# GSM.net
KiCad netlist of a schematic drawn in Altium Designer
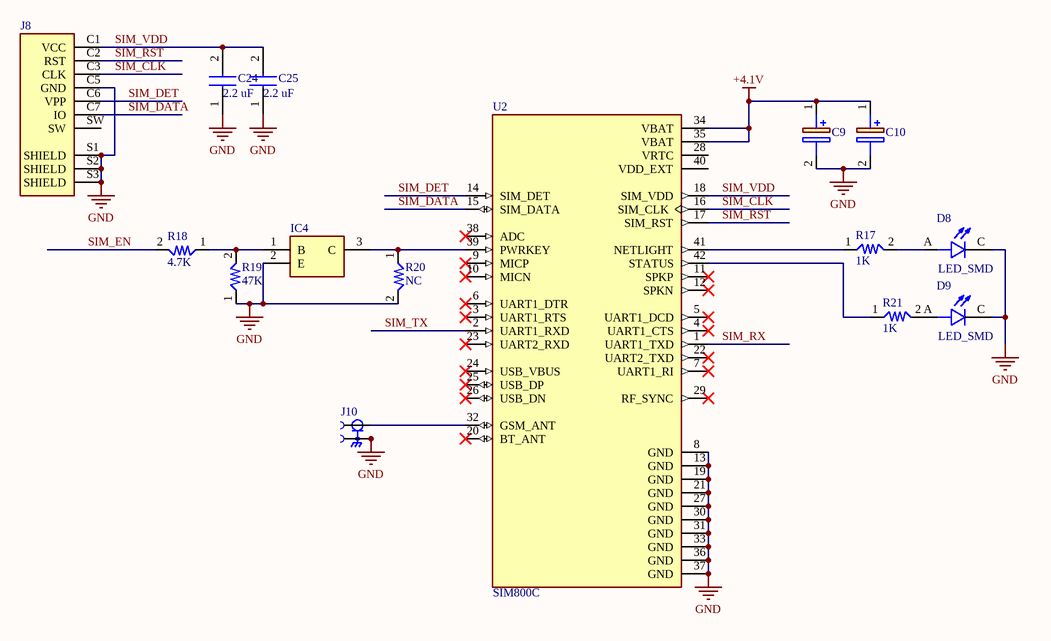
[diagram p0: GSM.SchDoc]

(export (version "E")
  (design (tool "Eeschema 10.0.6"))
  (components
    (comp (ref "C9")
      (value "TPSD227K010R0100")
      (footprint "SamacSys:CAPPM7344X310N")
      (description "Capacitor Polarised")
      (fields (field (name "MOUSER PART NUMBER") "581-TPSD227K010R0100"))
      (libsource (lib "*") (part "TPSD227K010R0100"))
    )
    (comp (ref "C10")
      (value "TPSD227K010R0100")
      (footprint "SamacSys:CAPPM7344X310N")
      (description "Capacitor Polarised")
      (fields (field (name "MOUSER PART NUMBER") "581-TPSD227K010R0100"))
      (libsource (lib "*") (part "TPSD227K010R0100"))
    )
    (comp (ref "C24")
      (value "2.2 uF")
      (footprint "CAP0603")
      (description "Capacitor")
      (fields
        (field (name "MANUFACTURER_PART_NUMBER") "CC0603KRX7R9BB104")
        (field (name "MOUSER PART NUMBER") "603-CC603KRX7R9BB104")
      )
      (libsource (lib "Valve_Controller_Lib") (part "CC0603KRX7R9BB104"))
    )
    (comp (ref "C25")
      (value "2.2 uF")
      (footprint "CAP0603")
      (description "Capacitor")
      (fields
        (field (name "MANUFACTURER_PART_NUMBER") "CC0603KRX7R9BB104")
        (field (name "MOUSER PART NUMBER") "603-CC603KRX7R9BB104")
      )
      (libsource (lib "Valve_Controller_Lib") (part "CC0603KRX7R9BB104"))
    )
    (comp (ref "D8")
      (value "LED_SMD")
      (footprint "LEDSC125X200X90-2N")
      (description "Red 633nm LED Indication - Discrete 2.1V 0805 (2012 Metric)")
      (fields (field (name "MF") "Dialight") (field (name "MP") "599-0110-007F"))
      (libsource (lib "Valve_Controller_Lib") (part "5990110007F"))
    )
    (comp (ref "D9")
      (value "LED_SMD")
      (footprint "LEDSC125X200X90-2N")
      (description "Red 633nm LED Indication - Discrete 2.1V 0805 (2012 Metric)")
      (fields (field (name "MF") "Dialight") (field (name "MP") "599-0110-007F"))
      (libsource (lib "Valve_Controller_Lib") (part "5990110007F"))
    )
    (comp (ref "IC4")
      (value "MMBT2222ALT1G")
      (footprint "SamacSys:SOT96P237X111-3N")
      (description "Integrated Circuit")
      (libsource (lib "*") (part "MMBT2222ALT1G"))
    )
    (comp (ref "J8")
      (value "SIM8060-6-1-14-00-A")
      (footprint "GCT_SIM8060-6-1-14-00-A")
      (description "6 Position Card Connector NANO SIM Surface Mount, Right Angle Gold")
      (fields (field (name "MF") "Global Connector Technology"))
      (libsource (lib "Valve_Controller_Lib") (part "SIM8060-6-1-14-00-A"))
    )
    (comp (ref "J10")
      (value "CONUFL001-SMD")
      (footprint "LINX_CONUFL001-SMD")
      (fields (field (name "MF") "Linx"))
      (libsource (lib "Valve_Controller_Lib") (part "CONUFL001-SMD"))
    )
    (comp (ref "R17")
      (value "1K")
      (footprint "RES0603")
      (description "Resistor")
      (fields (field (name "MANUFACTURER_PART_NUMBER") "0603WAF1001T5E"))
      (libsource (lib "Valve_Controller_Lib") (part "RES"))
    )
    (comp (ref "R18")
      (value "4.7K")
      (footprint "RES0603")
      (description "Resistor")
      (fields (field (name "MANUFACTURER_PART_NUMBER") "0603WAF1001T5E"))
      (libsource (lib "Valve_Controller_Lib") (part "RES"))
    )
    (comp (ref "R19")
      (value "47K")
      (footprint "RES0603")
      (description "Resistor")
      (fields (field (name "MANUFACTURER_PART_NUMBER") "0603WAF1001T5E"))
      (libsource (lib "Valve_Controller_Lib") (part "RES"))
    )
    (comp (ref "R20")
      (value "NC")
      (footprint "RES0603")
      (description "Resistor")
      (fields (field (name "MANUFACTURER_PART_NUMBER") "0603WAF1001T5E"))
      (libsource (lib "Valve_Controller_Lib") (part "RES"))
    )
    (comp (ref "R21")
      (value "1K")
      (footprint "RES0603")
      (description "Resistor")
      (fields (field (name "MANUFACTURER_PART_NUMBER") "0603WAF1001T5E"))
      (libsource (lib "Valve_Controller_Lib") (part "RES"))
    )
    (comp (ref "U2")
      (value "SIM800C")
      (footprint "LCC110P1570X1760X250-42N")
      (description "Module: GSM/Bluetooth; GPRS; 2G; 1800MHz, 900MHz; 85.6kbps; SMD")
      (fields (field (name "MF") "Simcom"))
      (libsource (lib "Valve_Controller_Lib") (part "SIM800C"))
    )
  )
  (nets
    (net (code "1") (name "+4.1V") (class "Default")
      (node (ref "C10") (pin "1") (pinfunction "+_1") (pintype "passive"))
      (node (ref "C9") (pin "1") (pinfunction "+_1") (pintype "passive"))
      (node (ref "U2") (pin "34") (pinfunction "VBAT_34") (pintype "power_in"))
      (node (ref "U2") (pin "35") (pinfunction "VBAT_35") (pintype "power_in"))
    )
    (net (code "2") (name "/SIM_CLK") (class "Default")
      (node (ref "J8") (pin "C3") (pinfunction "CLK_C3") (pintype "passive"))
      (node (ref "U2") (pin "16") (pinfunction "SIM_CLK_16") (pintype "output"))
    )
    (net (code "3") (name "/SIM_DATA") (class "Default")
      (node (ref "J8") (pin "C7") (pinfunction "IO_C7") (pintype "passive"))
      (node (ref "U2") (pin "15") (pinfunction "SIM_DATA_15") (pintype "bidirectional"))
    )
    (net (code "4") (name "/SIM_DET") (class "Default")
      (node (ref "J8") (pin "C6") (pinfunction "VPP_C6") (pintype "passive"))
      (node (ref "U2") (pin "14") (pinfunction "SIM_DET_14") (pintype "input"))
    )
    (net (code "5") (name "/SIM_EN") (class "Default")
      (node (ref "R18") (pin "2") (pinfunction "2_2") (pintype "passive"))
    )
    (net (code "6") (name "/SIM_RST") (class "Default")
      (node (ref "J8") (pin "C2") (pinfunction "RST_C2") (pintype "passive"))
      (node (ref "U2") (pin "17") (pinfunction "SIM_RST_17") (pintype "output"))
    )
    (net (code "7") (name "/SIM_RX") (class "Default")
      (node (ref "U2") (pin "1") (pinfunction "UART1_TXD_1") (pintype "output"))
    )
    (net (code "8") (name "/SIM_TX") (class "Default")
      (node (ref "U2") (pin "2") (pinfunction "UART1_RXD_2") (pintype "input"))
    )
    (net (code "9") (name "/SIM_VDD") (class "Default")
      (node (ref "C24") (pin "2") (pinfunction "2_2") (pintype "passive"))
      (node (ref "C25") (pin "2") (pinfunction "2_2") (pintype "passive"))
      (node (ref "J8") (pin "C1") (pinfunction "VCC_C1") (pintype "passive"))
      (node (ref "U2") (pin "18") (pinfunction "SIM_VDD_18") (pintype "output"))
    )
    (net (code "10") (name "GND") (class "Default")
      (node (ref "C10") (pin "2") (pinfunction "-_2") (pintype "passive"))
      (node (ref "C24") (pin "1") (pinfunction "1_1") (pintype "passive"))
      (node (ref "C25") (pin "1") (pinfunction "1_1") (pintype "passive"))
      (node (ref "C9") (pin "2") (pinfunction "-_2") (pintype "passive"))
      (node (ref "D8") (pin "C") (pinfunction "C_C") (pintype "passive"))
      (node (ref "D9") (pin "C") (pinfunction "C_C") (pintype "passive"))
      (node (ref "IC4") (pin "2") (pinfunction "E_2") (pintype "passive"))
      (node (ref "J10") (pin "2") (pinfunction "2_2") (pintype "passive"))
      (node (ref "J10") (pin "3") (pinfunction "2_3") (pintype "passive"))
      (node (ref "J8") (pin "C5") (pinfunction "GND_C5") (pintype "passive"))
      (node (ref "J8") (pin "S1") (pinfunction "SHIELD_S1") (pintype "passive"))
      (node (ref "J8") (pin "S2") (pinfunction "SHIELD_S2") (pintype "passive"))
      (node (ref "J8") (pin "S3") (pinfunction "SHIELD_S3") (pintype "passive"))
      (node (ref "R19") (pin "1") (pinfunction "1_1") (pintype "passive"))
      (node (ref "R20") (pin "2") (pinfunction "2_2") (pintype "passive"))
      (node (ref "U2") (pin "13") (pinfunction "GND_13") (pintype "power_in"))
      (node (ref "U2") (pin "19") (pinfunction "GND_19") (pintype "power_in"))
      (node (ref "U2") (pin "21") (pinfunction "GND_21") (pintype "power_in"))
      (node (ref "U2") (pin "27") (pinfunction "GND_27") (pintype "power_in"))
      (node (ref "U2") (pin "30") (pinfunction "GND_30") (pintype "power_in"))
      (node (ref "U2") (pin "31") (pinfunction "GND_31") (pintype "power_in"))
      (node (ref "U2") (pin "33") (pinfunction "GND_33") (pintype "power_in"))
      (node (ref "U2") (pin "36") (pinfunction "GND_36") (pintype "power_in"))
      (node (ref "U2") (pin "37") (pinfunction "GND_37") (pintype "power_in"))
      (node (ref "U2") (pin "8") (pinfunction "GND_8") (pintype "power_in"))
    )
    (net (code "11") (name "Net-(D8-PadA)") (class "Default")
      (node (ref "D8") (pin "A") (pinfunction "A_A") (pintype "passive"))
      (node (ref "R17") (pin "2") (pinfunction "2_2") (pintype "passive"))
    )
    (net (code "12") (name "Net-(D9-PadA)") (class "Default")
      (node (ref "D9") (pin "A") (pinfunction "A_A") (pintype "passive"))
      (node (ref "R21") (pin "2") (pinfunction "2_2") (pintype "passive"))
    )
    (net (code "13") (name "Net-(IC4-B)") (class "Default")
      (node (ref "IC4") (pin "1") (pinfunction "B_1") (pintype "passive"))
      (node (ref "R18") (pin "1") (pinfunction "1_1") (pintype "passive"))
      (node (ref "R19") (pin "2") (pinfunction "2_2") (pintype "passive"))
    )
    (net (code "14") (name "Net-(IC4-C)") (class "Default")
      (node (ref "IC4") (pin "3") (pinfunction "C_3") (pintype "passive"))
      (node (ref "R20") (pin "1") (pinfunction "1_1") (pintype "passive"))
      (node (ref "U2") (pin "39") (pinfunction "PWRKEY_39") (pintype "input"))
    )
    (net (code "15") (name "Net-(U2-GSM_ANT)") (class "Default")
      (node (ref "J10") (pin "1") (pinfunction "1_1") (pintype "passive"))
      (node (ref "U2") (pin "32") (pinfunction "GSM_ANT_32") (pintype "bidirectional"))
    )
    (net (code "16") (name "Net-(U2-NETLIGHT)") (class "Default")
      (node (ref "R17") (pin "1") (pinfunction "1_1") (pintype "passive"))
      (node (ref "U2") (pin "41") (pinfunction "NETLIGHT_41") (pintype "output"))
    )
    (net (code "17") (name "Net-(U2-STATUS)") (class "Default")
      (node (ref "R21") (pin "1") (pinfunction "1_1") (pintype "passive"))
      (node (ref "U2") (pin "42") (pinfunction "STATUS_42") (pintype "output"))
    )
    (net (code "18") (name "unconnected-(J8-PadSW)") (class "Default")
      (node (ref "J8") (pin "SW") (pinfunction "SW_SW") (pintype "passive"))
    )
    (net (code "19") (name "unconnected-(U2-ADC-Pad38)") (class "Default")
      (node (ref "U2") (pin "38") (pinfunction "ADC_38") (pintype "input+no_connect"))
    )
    (net (code "20") (name "unconnected-(U2-BT_ANT-Pad20)") (class "Default")
      (node (ref "U2") (pin "20") (pinfunction "BT_ANT_20") (pintype "bidirectional+no_connect"))
    )
    (net (code "21") (name "unconnected-(U2-MICN-Pad10)") (class "Default")
      (node (ref "U2") (pin "10") (pinfunction "MICN_10") (pintype "input+no_connect"))
    )
    (net (code "22") (name "unconnected-(U2-MICP-Pad9)") (class "Default")
      (node (ref "U2") (pin "9") (pinfunction "MICP_9") (pintype "input+no_connect"))
    )
    (net (code "23") (name "unconnected-(U2-RF_SYNC-Pad29)") (class "Default")
      (node (ref "U2") (pin "29") (pinfunction "RF_SYNC_29") (pintype "output+no_connect"))
    )
    (net (code "24") (name "unconnected-(U2-SPKN-Pad12)") (class "Default")
      (node (ref "U2") (pin "12") (pinfunction "SPKN_12") (pintype "output+no_connect"))
    )
    (net (code "25") (name "unconnected-(U2-SPKP-Pad11)") (class "Default")
      (node (ref "U2") (pin "11") (pinfunction "SPKP_11") (pintype "output+no_connect"))
    )
    (net (code "26") (name "unconnected-(U2-UART1_CTS-Pad4)") (class "Default")
      (node (ref "U2") (pin "4") (pinfunction "UART1_CTS_4") (pintype "output+no_connect"))
    )
    (net (code "27") (name "unconnected-(U2-UART1_DCD-Pad5)") (class "Default")
      (node (ref "U2") (pin "5") (pinfunction "UART1_DCD_5") (pintype "output+no_connect"))
    )
    (net (code "28") (name "unconnected-(U2-UART1_DTR-Pad6)") (class "Default")
      (node (ref "U2") (pin "6") (pinfunction "UART1_DTR_6") (pintype "input+no_connect"))
    )
    (net (code "29") (name "unconnected-(U2-UART1_RI-Pad7)") (class "Default")
      (node (ref "U2") (pin "7") (pinfunction "UART1_RI_7") (pintype "output+no_connect"))
    )
    (net (code "30") (name "unconnected-(U2-UART1_RTS-Pad3)") (class "Default")
      (node (ref "U2") (pin "3") (pinfunction "UART1_RTS_3") (pintype "input+no_connect"))
    )
    (net (code "31") (name "unconnected-(U2-UART2_RXD-Pad23)") (class "Default")
      (node (ref "U2") (pin "23") (pinfunction "UART2_RXD_23") (pintype "input+no_connect"))
    )
    (net (code "32") (name "unconnected-(U2-UART2_TXD-Pad22)") (class "Default")
      (node (ref "U2") (pin "22") (pinfunction "UART2_TXD_22") (pintype "output+no_connect"))
    )
    (net (code "33") (name "unconnected-(U2-USB_DN-Pad26)") (class "Default")
      (node (ref "U2") (pin "26") (pinfunction "USB_DN_26") (pintype "bidirectional+no_connect"))
    )
    (net (code "34") (name "unconnected-(U2-USB_DP-Pad25)") (class "Default")
      (node (ref "U2") (pin "25") (pinfunction "USB_DP_25") (pintype "bidirectional+no_connect"))
    )
    (net (code "35") (name "unconnected-(U2-USB_VBUS-Pad24)") (class "Default")
      (node (ref "U2") (pin "24") (pinfunction "USB_VBUS_24") (pintype "input+no_connect"))
    )
    (net (code "36") (name "unconnected-(U2-VDD_EXT-Pad40)") (class "Default")
      (node (ref "U2") (pin "40") (pinfunction "VDD_EXT_40") (pintype "power_in"))
    )
    (net (code "37") (name "unconnected-(U2-VRTC-Pad28)") (class "Default")
      (node (ref "U2") (pin "28") (pinfunction "VRTC_28") (pintype "power_in"))
    )
  )
)
